# touch-24-v5.net
KiCad netlist of a schematic drawn in Altium Designer
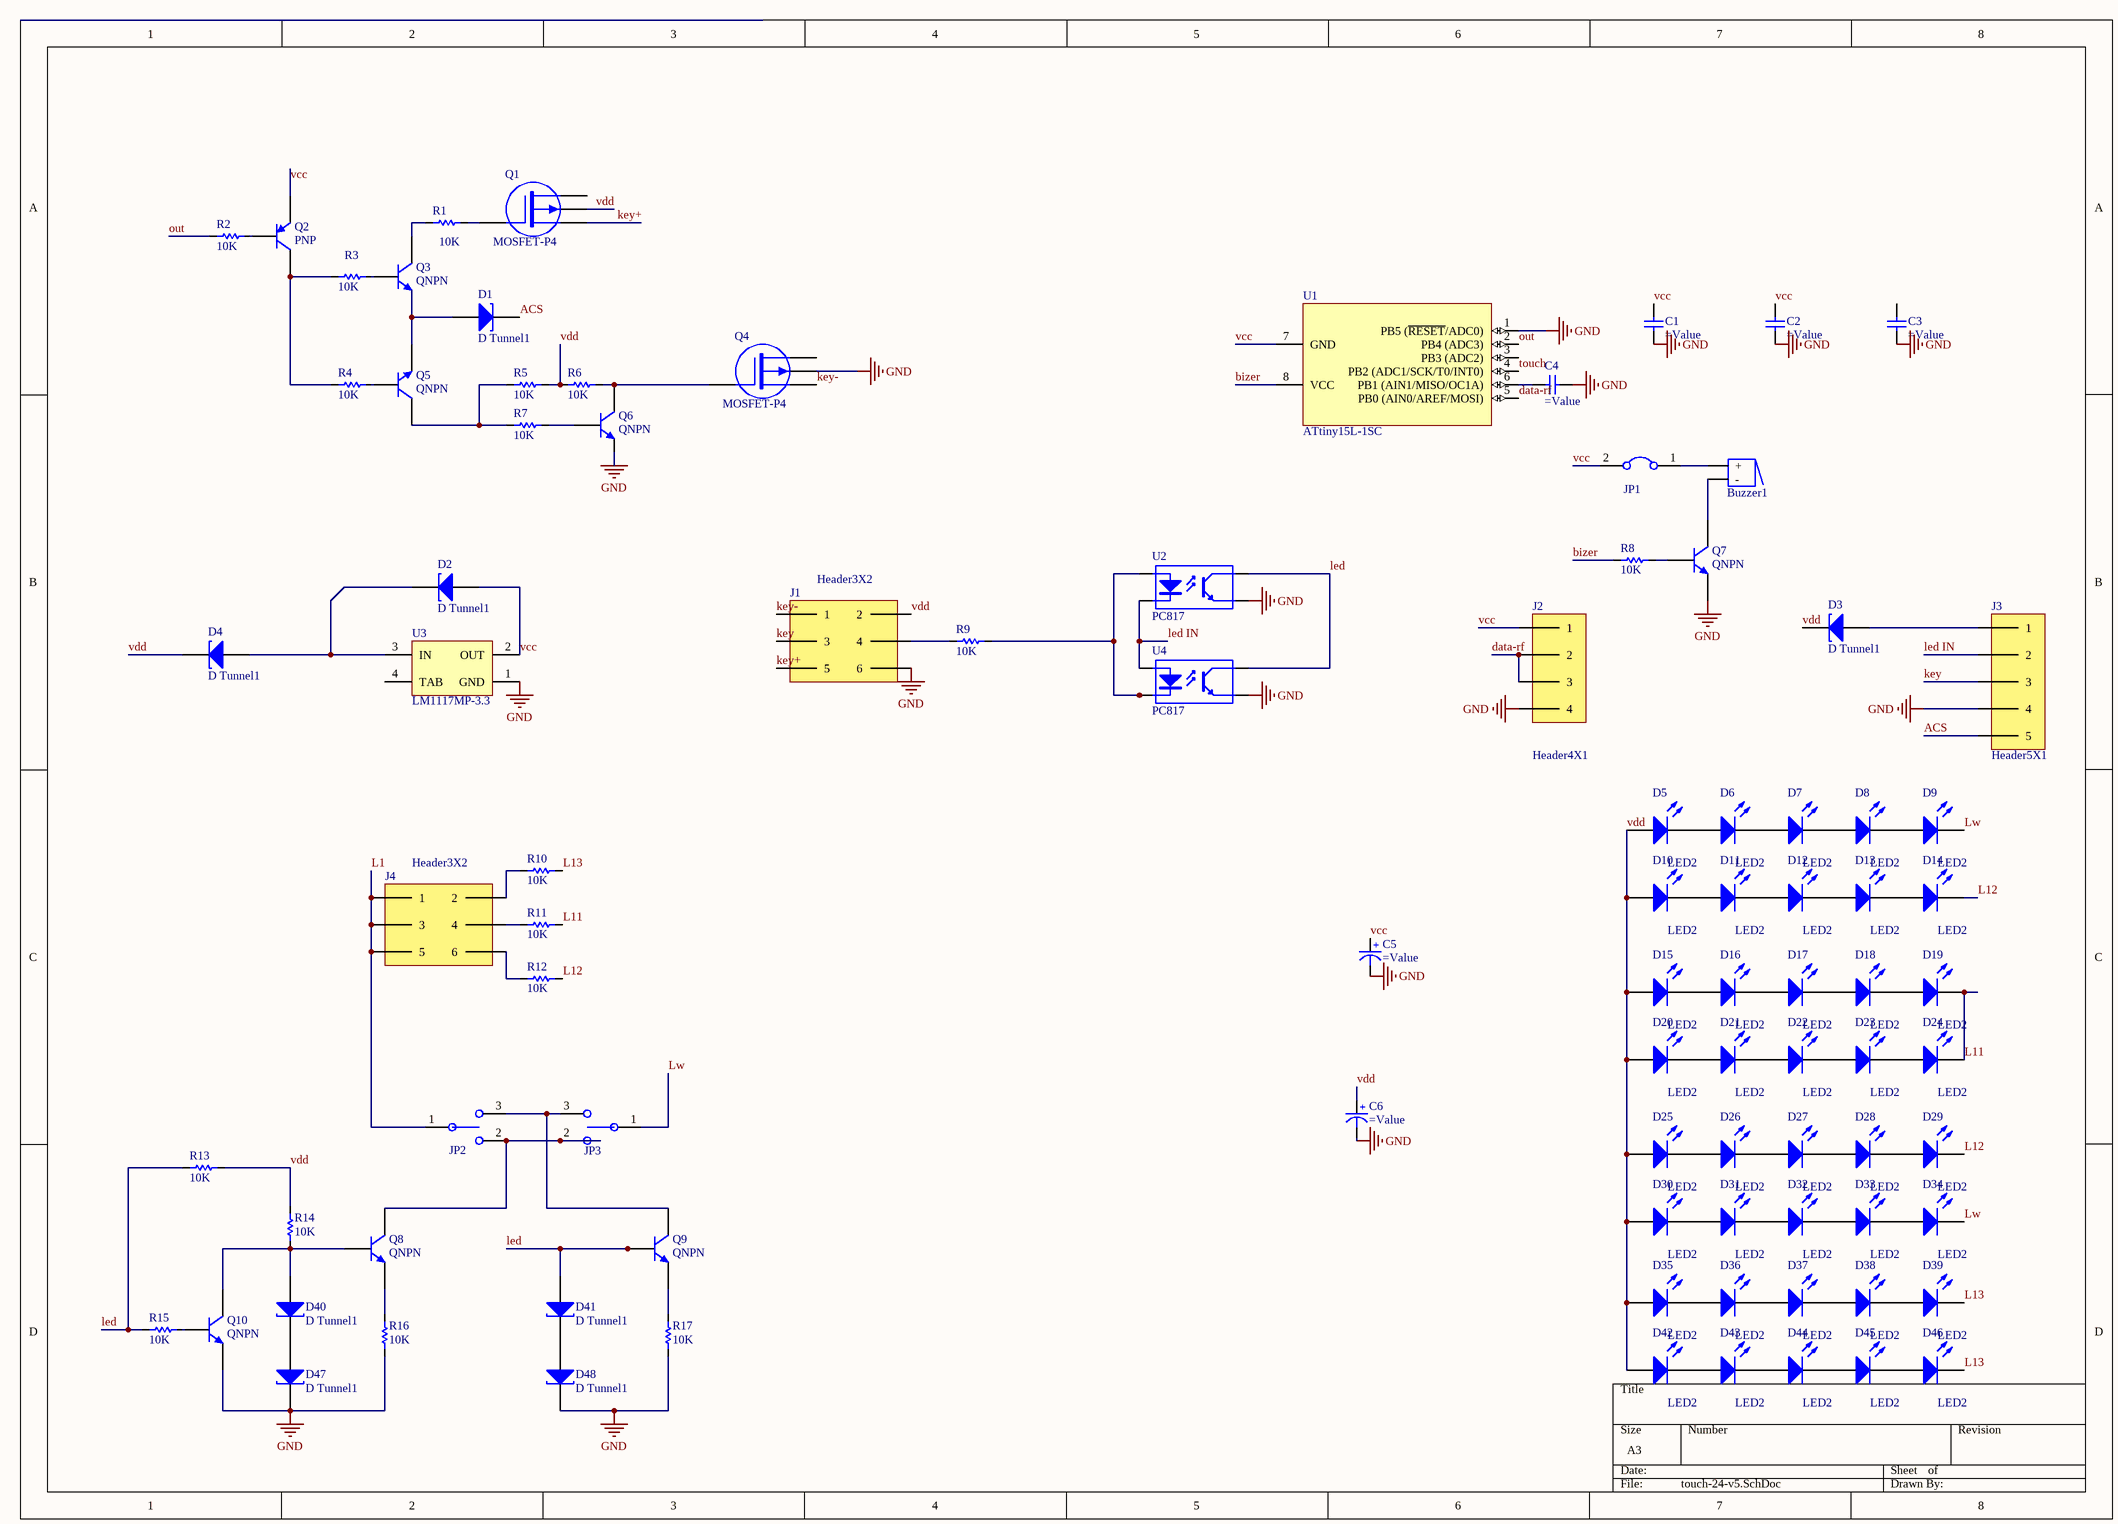
[diagram p0: touch-24-v5.SchDoc]

(export (version "E")
  (design (tool "Eeschema 10.0.6"))
  (components
    (comp (ref "Buzzer1")
      (value "Buzzer")
      (footprint "BUZZER")
      (fields (field (name "DESIGNER") "Seyed Mohsen Ghasemain"))
      (libsource (lib "PicPars.com_usefully_Library") (part "Buzzer"))
    )
    (comp (ref "C1")
      (value "~")
      (footprint "CAP 1206")
      (description "Capacitor")
      (libsource (lib "AltiumLib1") (part "Capacitor"))
    )
    (comp (ref "C2")
      (value "~")
      (footprint "CAP 1206")
      (description "Capacitor")
      (libsource (lib "AltiumLib1") (part "Capacitor"))
    )
    (comp (ref "C3")
      (value "~")
      (footprint "CAP 1206")
      (description "Capacitor")
      (libsource (lib "AltiumLib1") (part "Capacitor"))
    )
    (comp (ref "C4")
      (value "~")
      (footprint "CAP 1206")
      (description "Capacitor")
      (libsource (lib "AltiumLib1") (part "Capacitor"))
    )
    (comp (ref "C5")
      (value "~")
      (footprint "ELEC-CAP-RAD10-20")
      (description "Electrolytic Capacitor")
      (libsource (lib "AltiumLib1") (part "Capacitor Electrolytic"))
    )
    (comp (ref "C6")
      (value "~")
      (footprint "ELEC-CAP-RAD15-30")
      (description "Electrolytic Capacitor")
      (libsource (lib "AltiumLib1") (part "Capacitor Electrolytic"))
    )
    (comp (ref "D1")
      (value "D Tunnel1")
      (footprint "3.2X1.6X1.1")
      (description "Tunnel Diode - RLC Model")
      (fields (field (name "PUBLISHER") "Altium Limited"))
      (libsource (lib "Miscellaneous Devices") (part "D Tunnel1"))
    )
    (comp (ref "D2")
      (value "D Tunnel1")
      (footprint "3.2X1.6X1.1")
      (description "Tunnel Diode - RLC Model")
      (fields (field (name "PUBLISHER") "Altium Limited"))
      (libsource (lib "Miscellaneous Devices") (part "D Tunnel1"))
    )
    (comp (ref "D3")
      (value "D Tunnel1")
      (footprint "3.2X1.6X1.1")
      (description "Tunnel Diode - RLC Model")
      (fields (field (name "PUBLISHER") "Altium Limited"))
      (libsource (lib "Miscellaneous Devices") (part "D Tunnel1"))
    )
    (comp (ref "D4")
      (value "D Tunnel1")
      (footprint "3.2X1.6X1.1")
      (description "Tunnel Diode - RLC Model")
      (fields (field (name "PUBLISHER") "Altium Limited"))
      (libsource (lib "Miscellaneous Devices") (part "D Tunnel1"))
    )
    (comp (ref "D5")
      (value "LED2")
      (footprint "RES 0805 (2012X06L)")
      (description "Typical RED, GREEN, YELLOW, AMBER GaAs LED")
      (fields (field (name "PUBLISHER") "Altium Limited"))
      (libsource (lib "Miscellaneous Devices") (part "LED2"))
    )
    (comp (ref "D6")
      (value "LED2")
      (footprint "RES 0805 (2012X06L)")
      (description "Typical RED, GREEN, YELLOW, AMBER GaAs LED")
      (fields (field (name "PUBLISHER") "Altium Limited"))
      (libsource (lib "Miscellaneous Devices") (part "LED2"))
    )
    (comp (ref "D7")
      (value "LED2")
      (footprint "RES 0805 (2012X06L)")
      (description "Typical RED, GREEN, YELLOW, AMBER GaAs LED")
      (fields (field (name "PUBLISHER") "Altium Limited"))
      (libsource (lib "Miscellaneous Devices") (part "LED2"))
    )
    (comp (ref "D8")
      (value "LED2")
      (footprint "RES 0805 (2012X06L)")
      (description "Typical RED, GREEN, YELLOW, AMBER GaAs LED")
      (fields (field (name "PUBLISHER") "Altium Limited"))
      (libsource (lib "Miscellaneous Devices") (part "LED2"))
    )
    (comp (ref "D9")
      (value "LED2")
      (footprint "RES 0805 (2012X06L)")
      (description "Typical RED, GREEN, YELLOW, AMBER GaAs LED")
      (fields (field (name "PUBLISHER") "Altium Limited"))
      (libsource (lib "Miscellaneous Devices") (part "LED2"))
    )
    (comp (ref "D10")
      (value "LED2")
      (footprint "RES 0805 (2012X06L)")
      (description "Typical RED, GREEN, YELLOW, AMBER GaAs LED")
      (fields (field (name "PUBLISHER") "Altium Limited"))
      (libsource (lib "Miscellaneous Devices") (part "LED2"))
    )
    (comp (ref "D11")
      (value "LED2")
      (footprint "RES 0805 (2012X06L)")
      (description "Typical RED, GREEN, YELLOW, AMBER GaAs LED")
      (fields (field (name "PUBLISHER") "Altium Limited"))
      (libsource (lib "Miscellaneous Devices") (part "LED2"))
    )
    (comp (ref "D12")
      (value "LED2")
      (footprint "RES 0805 (2012X06L)")
      (description "Typical RED, GREEN, YELLOW, AMBER GaAs LED")
      (fields (field (name "PUBLISHER") "Altium Limited"))
      (libsource (lib "Miscellaneous Devices") (part "LED2"))
    )
    (comp (ref "D13")
      (value "LED2")
      (footprint "RES 0805 (2012X06L)")
      (description "Typical RED, GREEN, YELLOW, AMBER GaAs LED")
      (fields (field (name "PUBLISHER") "Altium Limited"))
      (libsource (lib "Miscellaneous Devices") (part "LED2"))
    )
    (comp (ref "D14")
      (value "LED2")
      (footprint "RES 0805 (2012X06L)")
      (description "Typical RED, GREEN, YELLOW, AMBER GaAs LED")
      (fields (field (name "PUBLISHER") "Altium Limited"))
      (libsource (lib "Miscellaneous Devices") (part "LED2"))
    )
    (comp (ref "D15")
      (value "LED2")
      (footprint "RES 0805 (2012X06L)")
      (description "Typical RED, GREEN, YELLOW, AMBER GaAs LED")
      (fields (field (name "PUBLISHER") "Altium Limited"))
      (libsource (lib "Miscellaneous Devices") (part "LED2"))
    )
    (comp (ref "D16")
      (value "LED2")
      (footprint "RES 0805 (2012X06L)")
      (description "Typical RED, GREEN, YELLOW, AMBER GaAs LED")
      (fields (field (name "PUBLISHER") "Altium Limited"))
      (libsource (lib "Miscellaneous Devices") (part "LED2"))
    )
    (comp (ref "D17")
      (value "LED2")
      (footprint "RES 0805 (2012X06L)")
      (description "Typical RED, GREEN, YELLOW, AMBER GaAs LED")
      (fields (field (name "PUBLISHER") "Altium Limited"))
      (libsource (lib "Miscellaneous Devices") (part "LED2"))
    )
    (comp (ref "D18")
      (value "LED2")
      (footprint "RES 0805 (2012X06L)")
      (description "Typical RED, GREEN, YELLOW, AMBER GaAs LED")
      (fields (field (name "PUBLISHER") "Altium Limited"))
      (libsource (lib "Miscellaneous Devices") (part "LED2"))
    )
    (comp (ref "D19")
      (value "LED2")
      (footprint "RES 0805 (2012X06L)")
      (description "Typical RED, GREEN, YELLOW, AMBER GaAs LED")
      (fields (field (name "PUBLISHER") "Altium Limited"))
      (libsource (lib "Miscellaneous Devices") (part "LED2"))
    )
    (comp (ref "D20")
      (value "LED2")
      (footprint "RES 0805 (2012X06L)")
      (description "Typical RED, GREEN, YELLOW, AMBER GaAs LED")
      (fields (field (name "PUBLISHER") "Altium Limited"))
      (libsource (lib "Miscellaneous Devices") (part "LED2"))
    )
    (comp (ref "D21")
      (value "LED2")
      (footprint "RES 0805 (2012X06L)")
      (description "Typical RED, GREEN, YELLOW, AMBER GaAs LED")
      (fields (field (name "PUBLISHER") "Altium Limited"))
      (libsource (lib "Miscellaneous Devices") (part "LED2"))
    )
    (comp (ref "D22")
      (value "LED2")
      (footprint "RES 0805 (2012X06L)")
      (description "Typical RED, GREEN, YELLOW, AMBER GaAs LED")
      (fields (field (name "PUBLISHER") "Altium Limited"))
      (libsource (lib "Miscellaneous Devices") (part "LED2"))
    )
    (comp (ref "D23")
      (value "LED2")
      (footprint "RES 0805 (2012X06L)")
      (description "Typical RED, GREEN, YELLOW, AMBER GaAs LED")
      (fields (field (name "PUBLISHER") "Altium Limited"))
      (libsource (lib "Miscellaneous Devices") (part "LED2"))
    )
    (comp (ref "D24")
      (value "LED2")
      (footprint "RES 0805 (2012X06L)")
      (description "Typical RED, GREEN, YELLOW, AMBER GaAs LED")
      (fields (field (name "PUBLISHER") "Altium Limited"))
      (libsource (lib "Miscellaneous Devices") (part "LED2"))
    )
    (comp (ref "D25")
      (value "LED2")
      (footprint "RES 0805 (2012X06L)")
      (description "Typical RED, GREEN, YELLOW, AMBER GaAs LED")
      (fields (field (name "PUBLISHER") "Altium Limited"))
      (libsource (lib "Miscellaneous Devices") (part "LED2"))
    )
    (comp (ref "D26")
      (value "LED2")
      (footprint "RES 0805 (2012X06L)")
      (description "Typical RED, GREEN, YELLOW, AMBER GaAs LED")
      (fields (field (name "PUBLISHER") "Altium Limited"))
      (libsource (lib "Miscellaneous Devices") (part "LED2"))
    )
    (comp (ref "D27")
      (value "LED2")
      (footprint "RES 0805 (2012X06L)")
      (description "Typical RED, GREEN, YELLOW, AMBER GaAs LED")
      (fields (field (name "PUBLISHER") "Altium Limited"))
      (libsource (lib "Miscellaneous Devices") (part "LED2"))
    )
    (comp (ref "D28")
      (value "LED2")
      (footprint "RES 0805 (2012X06L)")
      (description "Typical RED, GREEN, YELLOW, AMBER GaAs LED")
      (fields (field (name "PUBLISHER") "Altium Limited"))
      (libsource (lib "Miscellaneous Devices") (part "LED2"))
    )
    (comp (ref "D29")
      (value "LED2")
      (footprint "RES 0805 (2012X06L)")
      (description "Typical RED, GREEN, YELLOW, AMBER GaAs LED")
      (fields (field (name "PUBLISHER") "Altium Limited"))
      (libsource (lib "Miscellaneous Devices") (part "LED2"))
    )
    (comp (ref "D30")
      (value "LED2")
      (footprint "RES 0805 (2012X06L)")
      (description "Typical RED, GREEN, YELLOW, AMBER GaAs LED")
      (fields (field (name "PUBLISHER") "Altium Limited"))
      (libsource (lib "Miscellaneous Devices") (part "LED2"))
    )
    (comp (ref "D31")
      (value "LED2")
      (footprint "RES 0805 (2012X06L)")
      (description "Typical RED, GREEN, YELLOW, AMBER GaAs LED")
      (fields (field (name "PUBLISHER") "Altium Limited"))
      (libsource (lib "Miscellaneous Devices") (part "LED2"))
    )
    (comp (ref "D32")
      (value "LED2")
      (footprint "RES 0805 (2012X06L)")
      (description "Typical RED, GREEN, YELLOW, AMBER GaAs LED")
      (fields (field (name "PUBLISHER") "Altium Limited"))
      (libsource (lib "Miscellaneous Devices") (part "LED2"))
    )
    (comp (ref "D33")
      (value "LED2")
      (footprint "RES 0805 (2012X06L)")
      (description "Typical RED, GREEN, YELLOW, AMBER GaAs LED")
      (fields (field (name "PUBLISHER") "Altium Limited"))
      (libsource (lib "Miscellaneous Devices") (part "LED2"))
    )
    (comp (ref "D34")
      (value "LED2")
      (footprint "RES 0805 (2012X06L)")
      (description "Typical RED, GREEN, YELLOW, AMBER GaAs LED")
      (fields (field (name "PUBLISHER") "Altium Limited"))
      (libsource (lib "Miscellaneous Devices") (part "LED2"))
    )
    (comp (ref "D35")
      (value "LED2")
      (footprint "RES 0805 (2012X06L)")
      (description "Typical RED, GREEN, YELLOW, AMBER GaAs LED")
      (fields (field (name "PUBLISHER") "Altium Limited"))
      (libsource (lib "Miscellaneous Devices") (part "LED2"))
    )
    (comp (ref "D36")
      (value "LED2")
      (footprint "RES 0805 (2012X06L)")
      (description "Typical RED, GREEN, YELLOW, AMBER GaAs LED")
      (fields (field (name "PUBLISHER") "Altium Limited"))
      (libsource (lib "Miscellaneous Devices") (part "LED2"))
    )
    (comp (ref "D37")
      (value "LED2")
      (footprint "RES 0805 (2012X06L)")
      (description "Typical RED, GREEN, YELLOW, AMBER GaAs LED")
      (fields (field (name "PUBLISHER") "Altium Limited"))
      (libsource (lib "Miscellaneous Devices") (part "LED2"))
    )
    (comp (ref "D38")
      (value "LED2")
      (footprint "RES 0805 (2012X06L)")
      (description "Typical RED, GREEN, YELLOW, AMBER GaAs LED")
      (fields (field (name "PUBLISHER") "Altium Limited"))
      (libsource (lib "Miscellaneous Devices") (part "LED2"))
    )
    (comp (ref "D39")
      (value "LED2")
      (footprint "RES 0805 (2012X06L)")
      (description "Typical RED, GREEN, YELLOW, AMBER GaAs LED")
      (fields (field (name "PUBLISHER") "Altium Limited"))
      (libsource (lib "Miscellaneous Devices") (part "LED2"))
    )
    (comp (ref "D40")
      (value "D Tunnel1")
      (footprint "3.2X1.6X1.1")
      (description "Tunnel Diode - RLC Model")
      (fields (field (name "PUBLISHER") "Altium Limited"))
      (libsource (lib "Miscellaneous Devices") (part "D Tunnel1"))
    )
    (comp (ref "D41")
      (value "D Tunnel1")
      (footprint "3.2X1.6X1.1")
      (description "Tunnel Diode - RLC Model")
      (fields (field (name "PUBLISHER") "Altium Limited"))
      (libsource (lib "Miscellaneous Devices") (part "D Tunnel1"))
    )
    (comp (ref "D42")
      (value "LED2")
      (footprint "RES 0805 (2012X06L)")
      (description "Typical RED, GREEN, YELLOW, AMBER GaAs LED")
      (fields (field (name "PUBLISHER") "Altium Limited"))
      (libsource (lib "Miscellaneous Devices") (part "LED2"))
    )
    (comp (ref "D43")
      (value "LED2")
      (footprint "RES 0805 (2012X06L)")
      (description "Typical RED, GREEN, YELLOW, AMBER GaAs LED")
      (fields (field (name "PUBLISHER") "Altium Limited"))
      (libsource (lib "Miscellaneous Devices") (part "LED2"))
    )
    (comp (ref "D44")
      (value "LED2")
      (footprint "RES 0805 (2012X06L)")
      (description "Typical RED, GREEN, YELLOW, AMBER GaAs LED")
      (fields (field (name "PUBLISHER") "Altium Limited"))
      (libsource (lib "Miscellaneous Devices") (part "LED2"))
    )
    (comp (ref "D45")
      (value "LED2")
      (footprint "RES 0805 (2012X06L)")
      (description "Typical RED, GREEN, YELLOW, AMBER GaAs LED")
      (fields (field (name "PUBLISHER") "Altium Limited"))
      (libsource (lib "Miscellaneous Devices") (part "LED2"))
    )
    (comp (ref "D46")
      (value "LED2")
      (footprint "RES 0805 (2012X06L)")
      (description "Typical RED, GREEN, YELLOW, AMBER GaAs LED")
      (fields (field (name "PUBLISHER") "Altium Limited"))
      (libsource (lib "Miscellaneous Devices") (part "LED2"))
    )
    (comp (ref "D47")
      (value "D Tunnel1")
      (footprint "3.2X1.6X1.1")
      (description "Tunnel Diode - RLC Model")
      (fields (field (name "PUBLISHER") "Altium Limited"))
      (libsource (lib "Miscellaneous Devices") (part "D Tunnel1"))
    )
    (comp (ref "D48")
      (value "D Tunnel1")
      (footprint "3.2X1.6X1.1")
      (description "Tunnel Diode - RLC Model")
      (fields (field (name "PUBLISHER") "Altium Limited"))
      (libsource (lib "Miscellaneous Devices") (part "D Tunnel1"))
    )
    (comp (ref "J1")
      (value "Header3X2")
      (footprint "HEADER 3X2")
      (libsource (lib "AltiumLib1") (part "Header3X2"))
    )
    (comp (ref "J2")
      (value "Header4X1")
      (footprint "HEADER 4X1")
      (libsource (lib "AltiumLib1") (part "Header4X1"))
    )
    (comp (ref "J3")
      (value "Header5X1")
      (footprint "HEADER 5X1")
      (libsource (lib "AltiumLib1") (part "Header5X1"))
    )
    (comp (ref "J4")
      (value "Header3X2")
      (footprint "HEADER 3X2")
      (libsource (lib "AltiumLib1") (part "Header3X2"))
    )
    (comp (ref "JP1")
      (value "Jumper")
      (footprint "Header 2X1")
      (libsource (lib "AltiumLib1") (part "Jumper"))
    )
    (comp (ref "JP2")
      (value "Jumper Selector")
      (footprint "Jumper Selector")
      (libsource (lib "") (part "Jumper Selector_1"))
    )
    (comp (ref "JP3")
      (value "Jumper Selector")
      (footprint "Jumper Selector")
      (libsource (lib "AltiumLib1") (part "Jumper Selector"))
    )
    (comp (ref "Q1")
      (value "MOSFET-P4")
      (footprint "SOT223_N")
      (description "P-Channel MOSFET, Externally Terminated Substrate")
      (fields (field (name "PUBLISHER") "Altium Limited"))
      (libsource (lib "Miscellaneous Devices") (part "MOSFET-P4"))
    )
    (comp (ref "Q2")
      (value "PNP")
      (footprint "SOT-23B_N")
      (description "PNP Bipolar Transistor")
      (fields (field (name "PUBLISHER") "Altium Limited"))
      (libsource (lib "Miscellaneous Devices") (part "PNP"))
    )
    (comp (ref "Q3")
      (value "QNPN")
      (footprint "SOT-23B_L")
      (description "NPN Bipolar Transistor")
      (fields (field (name "PUBLISHER") "Altium Limited"))
      (libsource (lib "Miscellaneous Devices") (part "QNPN"))
    )
    (comp (ref "Q4")
      (value "MOSFET-P4")
      (footprint "SOT223_N")
      (description "P-Channel MOSFET, Externally Terminated Substrate")
      (fields (field (name "PUBLISHER") "Altium Limited"))
      (libsource (lib "Miscellaneous Devices") (part "MOSFET-P4"))
    )
    (comp (ref "Q5")
      (value "QNPN")
      (footprint "SOT-23B_L")
      (description "NPN Bipolar Transistor")
      (fields (field (name "PUBLISHER") "Altium Limited"))
      (libsource (lib "Miscellaneous Devices") (part "QNPN"))
    )
    (comp (ref "Q6")
      (value "QNPN")
      (footprint "SOT-23B_L")
      (description "NPN Bipolar Transistor")
      (fields (field (name "PUBLISHER") "Altium Limited"))
      (libsource (lib "Miscellaneous Devices") (part "QNPN"))
    )
    (comp (ref "Q7")
      (value "QNPN")
      (footprint "SOT-23B_L")
      (description "NPN Bipolar Transistor")
      (fields (field (name "PUBLISHER") "Altium Limited"))
      (libsource (lib "Miscellaneous Devices") (part "QNPN"))
    )
    (comp (ref "Q8")
      (value "QNPN")
      (footprint "SOT-23B_L")
      (description "NPN Bipolar Transistor")
      (fields (field (name "PUBLISHER") "Altium Limited"))
      (libsource (lib "Miscellaneous Devices") (part "QNPN"))
    )
    (comp (ref "Q9")
      (value "QNPN")
      (footprint "SOT-23B_L")
      (description "NPN Bipolar Transistor")
      (fields (field (name "PUBLISHER") "Altium Limited"))
      (libsource (lib "Miscellaneous Devices") (part "QNPN"))
    )
    (comp (ref "Q10")
      (value "QNPN")
      (footprint "SOT-23B_L")
      (description "NPN Bipolar Transistor")
      (fields (field (name "PUBLISHER") "Altium Limited"))
      (libsource (lib "Miscellaneous Devices") (part "QNPN"))
    )
    (comp (ref "R1")
      (value "10K")
      (footprint "RES 1206 (3216X08L)")
      (description "Resistor")
      (fields (field (name "TOLERANCE") "5%") (field (name "POWER") "1/4 W"))
      (libsource (lib "AltiumLib1") (part "Resistor"))
    )
    (comp (ref "R2")
      (value "10K")
      (footprint "RES 1206 (3216X08L)")
      (description "Resistor")
      (fields (field (name "TOLERANCE") "5%") (field (name "POWER") "1/4 W"))
      (libsource (lib "AltiumLib1") (part "Resistor"))
    )
    (comp (ref "R3")
      (value "10K")
      (footprint "RES 1206 (3216X08L)")
      (description "Resistor")
      (fields (field (name "TOLERANCE") "5%") (field (name "POWER") "1/4 W"))
      (libsource (lib "AltiumLib1") (part "Resistor"))
    )
    (comp (ref "R4")
      (value "10K")
      (footprint "RES 1206 (3216X08L)")
      (description "Resistor")
      (fields (field (name "TOLERANCE") "5%") (field (name "POWER") "1/4 W"))
      (libsource (lib "AltiumLib1") (part "Resistor"))
    )
    (comp (ref "R5")
      (value "10K")
      (footprint "RES 1206 (3216X08L)")
      (description "Resistor")
      (fields (field (name "TOLERANCE") "5%") (field (name "POWER") "1/4 W"))
      (libsource (lib "AltiumLib1") (part "Resistor"))
    )
    (comp (ref "R6")
      (value "10K")
      (footprint "RES 1206 (3216X08L)")
      (description "Resistor")
      (fields (field (name "TOLERANCE") "5%") (field (name "POWER") "1/4 W"))
      (libsource (lib "AltiumLib1") (part "Resistor"))
    )
    (comp (ref "R7")
      (value "10K")
      (footprint "RES 1206 (3216X08L)")
      (description "Resistor")
      (fields (field (name "TOLERANCE") "5%") (field (name "POWER") "1/4 W"))
      (libsource (lib "AltiumLib1") (part "Resistor"))
    )
    (comp (ref "R8")
      (value "10K")
      (footprint "RES 1206 (3216X08L)")
      (description "Resistor")
      (fields (field (name "TOLERANCE") "5%") (field (name "POWER") "1/4 W"))
      (libsource (lib "AltiumLib1") (part "Resistor"))
    )
    (comp (ref "R9")
      (value "10K")
      (footprint "RES 1206 (3216X08L)")
      (description "Resistor")
      (fields (field (name "TOLERANCE") "5%") (field (name "POWER") "1/4 W"))
      (libsource (lib "AltiumLib1") (part "Resistor"))
    )
    (comp (ref "R10")
      (value "10K")
      (footprint "RES 1206 (3216X08L)")
      (description "Resistor")
      (fields (field (name "TOLERANCE") "5%") (field (name "POWER") "1/4 W"))
      (libsource (lib "AltiumLib1") (part "Resistor"))
    )
    (comp (ref "R11")
      (value "10K")
      (footprint "RES 1206 (3216X08L)")
      (description "Resistor")
      (fields (field (name "TOLERANCE") "5%") (field (name "POWER") "1/4 W"))
      (libsource (lib "AltiumLib1") (part "Resistor"))
    )
    (comp (ref "R12")
      (value "10K")
      (footprint "RES 1206 (3216X08L)")
      (description "Resistor")
      (fields (field (name "TOLERANCE") "5%") (field (name "POWER") "1/4 W"))
      (libsource (lib "AltiumLib1") (part "Resistor"))
    )
    (comp (ref "R13")
      (value "10K")
      (footprint "RES 1206 (3216X08L)")
      (description "Resistor")
      (fields (field (name "TOLERANCE") "5%") (field (name "POWER") "1/4 W"))
      (libsource (lib "AltiumLib1") (part "Resistor"))
    )
    (comp (ref "R14")
      (value "10K")
      (footprint "RES 1206 (3216X08L)")
      (description "Resistor")
      (fields (field (name "TOLERANCE") "5%") (field (name "POWER") "1/4 W"))
      (libsource (lib "AltiumLib1") (part "Resistor"))
    )
    (comp (ref "R15")
      (value "10K")
      (footprint "RES 1206 (3216X08L)")
      (description "Resistor")
      (fields (field (name "TOLERANCE") "5%") (field (name "POWER") "1/4 W"))
      (libsource (lib "AltiumLib1") (part "Resistor"))
    )
    (comp (ref "R16")
      (value "10K")
      (footprint "RES 1206 (3216X08L)")
      (description "Resistor")
      (fields (field (name "TOLERANCE") "5%") (field (name "POWER") "1/4 W"))
      (libsource (lib "AltiumLib1") (part "Resistor"))
    )
    (comp (ref "R17")
      (value "10K")
      (footprint "RES 1206 (3216X08L)")
      (description "Resistor")
      (fields (field (name "TOLERANCE") "5%") (field (name "POWER") "1/4 W"))
      (libsource (lib "AltiumLib1") (part "Resistor"))
    )
    (comp (ref "U1")
      (value "ATtiny15L-1SC")
      (footprint "8S2_N")
      (description "8-Bit AVR Microcontroller with 1K Byte of Flash Memory")
      (fields (field (name "PUBLISHER") "Altium Limited"))
      (libsource (lib "Atmel Microcontroller 8-Bit AVR") (part "ATtiny15L-1SC"))
    )
    (comp (ref "U2")
      (value "PC817")
      (footprint "DIP4")
      (description "4-Pin Phototransistor Optocoupler")
      (libsource (lib "AltiumLib1") (part "OPTCOUPLER_01"))
    )
    (comp (ref "U3")
      (value "LM1117MP-3.3")
      (footprint "Miscellaneous Devices:SOT89L")
      (description "800mA Low-Dropout Linear Regulator")
      (fields
        (field (name "MANUFACTURER") "National Semiconductor")
        (field (name "DIGIKEYPARTNUMBER") "LM1117MP-3.3CT-ND")
        (field (name "PUBLISHER") "Altium Limited")
      )
      (libsource (lib "NSC LDO") (part "LM1117MP-3.3"))
    )
    (comp (ref "U4")
      (value "PC817")
      (footprint "DIP4")
      (description "4-Pin Phototransistor Optocoupler")
      (libsource (lib "AltiumLib1") (part "OPTCOUPLER_01"))
    )
  )
  (nets
    (net (code "1") (name "/ACS") (class "Default")
      (node (ref "D1") (pin "2") (pinfunction "K_2") (pintype "passive"))
      (node (ref "J3") (pin "5") (pinfunction "5_5") (pintype "passive"))
    )
    (net (code "2") (name "/L1") (class "Default")
      (node (ref "J4") (pin "1") (pinfunction "1_1") (pintype "passive"))
      (node (ref "J4") (pin "3") (pinfunction "3_3") (pintype "passive"))
      (node (ref "J4") (pin "5") (pinfunction "5_5") (pintype "passive"))
      (node (ref "JP2") (pin "1") (pinfunction "1_1") (pintype "passive"))
    )
    (net (code "3") (name "/L11") (class "Default")
      (node (ref "D19") (pin "2") (pinfunction "K_2") (pintype "passive"))
      (node (ref "D24") (pin "2") (pinfunction "K_2") (pintype "passive"))
      (node (ref "R11") (pin "2") (pinfunction "2_2") (pintype "passive"))
    )
    (net (code "4") (name "/L12") (class "Default")
      (node (ref "D14") (pin "2") (pinfunction "K_2") (pintype "passive"))
      (node (ref "D29") (pin "2") (pinfunction "K_2") (pintype "passive"))
      (node (ref "R12") (pin "2") (pinfunction "2_2") (pintype "passive"))
    )
    (net (code "5") (name "/L13") (class "Default")
      (node (ref "D39") (pin "2") (pinfunction "K_2") (pintype "passive"))
      (node (ref "D46") (pin "2") (pinfunction "K_2") (pintype "passive"))
      (node (ref "R10") (pin "2") (pinfunction "2_2") (pintype "passive"))
    )
    (net (code "6") (name "/Lw") (class "Default")
      (node (ref "D34") (pin "2") (pinfunction "K_2") (pintype "passive"))
      (node (ref "D9") (pin "2") (pinfunction "K_2") (pintype "passive"))
      (node (ref "JP3") (pin "1") (pinfunction "1_1") (pintype "passive"))
    )
    (net (code "7") (name "/bizer") (class "Default")
      (node (ref "R8") (pin "1") (pinfunction "1_1") (pintype "passive"))
      (node (ref "U1") (pin "8") (pinfunction "VCC_8") (pintype "power_in"))
    )
    (net (code "8") (name "/data-rf") (class "Default")
      (node (ref "J2") (pin "2") (pinfunction "2_2") (pintype "passive"))
      (node (ref "J2") (pin "3") (pinfunction "3_3") (pintype "passive"))
      (node (ref "U1") (pin "5") (pinfunction "PB0_(AIN0/AREF/MOSI)_5") (pintype "bidirectional"))
    )
    (net (code "9") (name "/key") (class "Default")
      (node (ref "J1") (pin "3") (pinfunction "3_3") (pintype "passive"))
      (node (ref "J3") (pin "3") (pinfunction "3_3") (pintype "passive"))
    )
    (net (code "10") (name "/key+") (class "Default")
      (node (ref "J1") (pin "5") (pinfunction "5_5") (pintype "passive"))
      (node (ref "Q1") (pin "4") (pinfunction "S_4") (pintype "passive"))
    )
    (net (code "11") (name "/key-") (class "Default")
      (node (ref "J1") (pin "1") (pinfunction "1_1") (pintype "passive"))
      (node (ref "Q4") (pin "4") (pinfunction "S_4") (pintype "passive"))
    )
    (net (code "12") (name "/led") (class "Default")
      (node (ref "D41") (pin "1") (pinfunction "A_1") (pintype "passive"))
      (node (ref "Q9") (pin "2") (pinfunction "B_2") (pintype "passive"))
      (node (ref "R13") (pin "1") (pinfunction "1_1") (pintype "passive"))
      (node (ref "R15") (pin "1") (pinfunction "1_1") (pintype "passive"))
      (node (ref "U2") (pin "4") (pinfunction "C_4") (pintype "passive"))
      (node (ref "U4") (pin "4") (pinfunction "C_4") (pintype "passive"))
    )
    (net (code "13") (name "/led IN") (class "Default")
      (node (ref "J3") (pin "2") (pinfunction "2_2") (pintype "passive"))
      (node (ref "U2") (pin "2") (pinfunction "K_2") (pintype "passive"))
      (node (ref "U4") (pin "1") (pinfunction "A_1") (pintype "passive"))
    )
    (net (code "14") (name "/out") (class "Default")
      (node (ref "R2") (pin "1") (pinfunction "1_1") (pintype "passive"))
      (node (ref "U1") (pin "2") (pinfunction "PB4_(ADC3)_2") (pintype "bidirectional"))
    )
    (net (code "15") (name "/touch") (class "Default")
      (node (ref "U1") (pin "4") (pinfunction "PB2_(ADC1/SCK/T0/INT0)_4") (pintype "bidirectional"))
    )
    (net (code "16") (name "/vcc") (class "Default")
      (node (ref "C1") (pin "2") (pinfunction "-_2") (pintype "passive"))
      (node (ref "C2") (pin "2") (pinfunction "-_2") (pintype "passive"))
      (node (ref "C5") (pin "2") (pinfunction "+_2") (pintype "passive"))
      (node (ref "D2") (pin "1") (pinfunction "A_1") (pintype "passive"))
      (node (ref "J2") (pin "1") (pinfunction "1_1") (pintype "passive"))
      (node (ref "JP1") (pin "2") (pinfunction "2_2") (pintype "passive"))
      (node (ref "Q2") (pin "3") (pinfunction "E_3") (pintype "passive"))
      (node (ref "U1") (pin "7") (pinfunction "GND_7") (pintype "power_in"))
      (node (ref "U3") (pin "2") (pinfunction "OUT_2") (pintype "power_in"))
    )
    (net (code "17") (name "/vdd") (class "Default")
      (node (ref "C6") (pin "2") (pinfunction "+_2") (pintype "passive"))
      (node (ref "D10") (pin "1") (pinfunction "A_1") (pintype "passive"))
      (node (ref "D15") (pin "1") (pinfunction "A_1") (pintype "passive"))
      (node (ref "D20") (pin "1") (pinfunction "A_1") (pintype "passive"))
      (node (ref "D25") (pin "1") (pinfunction "A_1") (pintype "passive"))
      (node (ref "D3") (pin "2") (pinfunction "K_2") (pintype "passive"))
      (node (ref "D30") (pin "1") (pinfunction "A_1") (pintype "passive"))
      (node (ref "D35") (pin "1") (pinfunction "A_1") (pintype "passive"))
      (node (ref "D4") (pin "2") (pinfunction "K_2") (pintype "passive"))
      (node (ref "D42") (pin "1") (pinfunction "A_1") (pintype "passive"))
      (node (ref "D5") (pin "1") (pinfunction "A_1") (pintype "passive"))
      (node (ref "J1") (pin "2") (pinfunction "2_2") (pintype "passive"))
      (node (ref "Q1") (pin "3") (pinfunction "U_3") (pintype "passive"))
      (node (ref "R13") (pin "2") (pinfunction "2_2") (pintype "passive"))
      (node (ref "R14") (pin "2") (pinfunction "2_2") (pintype "passive"))
      (node (ref "R5") (pin "2") (pinfunction "2_2") (pintype "passive"))
      (node (ref "R6") (pin "1") (pinfunction "1_1") (pintype "passive"))
    )
    (net (code "18") (name "GND") (class "Default")
      (node (ref "C1") (pin "1") (pinfunction "+_1") (pintype "passive"))
      (node (ref "C2") (pin "1") (pinfunction "+_1") (pintype "passive"))
      (node (ref "C3") (pin "1") (pinfunction "+_1") (pintype "passive"))
      (node (ref "C4") (pin "1") (pinfunction "+_1") (pintype "passive"))
      (node (ref "C5") (pin "1") (pinfunction "-_1") (pintype "passive"))
      (node (ref "C6") (pin "1") (pinfunction "-_1") (pintype "passive"))
      (node (ref "D47") (pin "2") (pinfunction "K_2") (pintype "passive"))
      (node (ref "D48") (pin "2") (pinfunction "K_2") (pintype "passive"))
      (node (ref "J1") (pin "6") (pinfunction "6_6") (pintype "passive"))
      (node (ref "J2") (pin "4") (pinfunction "4_4") (pintype "passive"))
      (node (ref "J3") (pin "4") (pinfunction "4_4") (pintype "passive"))
      (node (ref "Q10") (pin "3") (pinfunction "E_3") (pintype "passive"))
      (node (ref "Q4") (pin "3") (pinfunction "U_3") (pintype "passive"))
      (node (ref "Q6") (pin "3") (pinfunction "E_3") (pintype "passive"))
      (node (ref "Q7") (pin "3") (pinfunction "E_3") (pintype "passive"))
      (node (ref "R16") (pin "1") (pinfunction "1_1") (pintype "passive"))
      (node (ref "R17") (pin "1") (pinfunction "1_1") (pintype "passive"))
      (node (ref "U1") (pin "1") (pinfunction "PB5_(~{RESET}/ADC0)_1") (pintype "bidirectional"))
      (node (ref "U2") (pin "3") (pinfunction "E_3") (pintype "passive"))
      (node (ref "U3") (pin "1") (pinfunction "GND_1") (pintype "power_in"))
      (node (ref "U4") (pin "3") (pinfunction "E_3") (pintype "passive"))
    )
    (net (code "19") (name "Net-(Buzzer1-+)") (class "Default")
      (node (ref "Buzzer1") (pin "1") (pinfunction "+_1") (pintype "passive"))
      (node (ref "JP1") (pin "1") (pinfunction "1_1") (pintype "passive"))
    )
    (net (code "20") (name "Net-(Buzzer1--)") (class "Default")
      (node (ref "Buzzer1") (pin "2") (pinfunction "-_2") (pintype "passive"))
      (node (ref "Q7") (pin "1") (pinfunction "C_1") (pintype "passive"))
    )
    (net (code "21") (name "Net-(C4--)") (class "Default")
      (node (ref "C4") (pin "2") (pinfunction "-_2") (pintype "passive"))
      (node (ref "U1") (pin "6") (pinfunction "PB1_(AIN1/MISO/OC1A)_6") (pintype "bidirectional"))
    )
    (net (code "22") (name "Net-(D1-A)") (class "Default")
      (node (ref "D1") (pin "1") (pinfunction "A_1") (pintype "passive"))
      (node (ref "Q3") (pin "3") (pinfunction "E_3") (pintype "passive"))
      (node (ref "Q5") (pin "3") (pinfunction "E_3") (pintype "passive"))
    )
    (net (code "23") (name "Net-(D2-K)") (class "Default")
      (node (ref "D2") (pin "2") (pinfunction "K_2") (pintype "passive"))
      (node (ref "D4") (pin "1") (pinfunction "A_1") (pintype "passive"))
      (node (ref "U3") (pin "3") (pinfunction "IN_3") (pintype "power_in"))
    )
    (net (code "24") (name "Net-(D3-A)") (class "Default")
      (node (ref "D3") (pin "1") (pinfunction "A_1") (pintype "passive"))
      (node (ref "J3") (pin "1") (pinfunction "1_1") (pintype "passive"))
    )
    (net (code "25") (name "Net-(D5-K)") (class "Default")
      (node (ref "D5") (pin "2") (pinfunction "K_2") (pintype "passive"))
      (node (ref "D6") (pin "1") (pinfunction "A_1") (pintype "passive"))
    )
    (net (code "26") (name "Net-(D6-K)") (class "Default")
      (node (ref "D6") (pin "2") (pinfunction "K_2") (pintype "passive"))
      (node (ref "D7") (pin "1") (pinfunction "A_1") (pintype "passive"))
    )
    (net (code "27") (name "Net-(D7-K)") (class "Default")
      (node (ref "D7") (pin "2") (pinfunction "K_2") (pintype "passive"))
      (node (ref "D8") (pin "1") (pinfunction "A_1") (pintype "passive"))
    )
    (net (code "28") (name "Net-(D8-K)") (class "Default")
      (node (ref "D8") (pin "2") (pinfunction "K_2") (pintype "passive"))
      (node (ref "D9") (pin "1") (pinfunction "A_1") (pintype "passive"))
    )
    (net (code "29") (name "Net-(D10-K)") (class "Default")
      (node (ref "D10") (pin "2") (pinfunction "K_2") (pintype "passive"))
      (node (ref "D11") (pin "1") (pinfunction "A_1") (pintype "passive"))
    )
    (net (code "30") (name "Net-(D11-K)") (class "Default")
      (node (ref "D11") (pin "2") (pinfunction "K_2") (pintype "passive"))
      (node (ref "D12") (pin "1") (pinfunction "A_1") (pintype "passive"))
    )
    (net (code "31") (name "Net-(D12-K)") (class "Default")
      (node (ref "D12") (pin "2") (pinfunction "K_2") (pintype "passive"))
      (node (ref "D13") (pin "1") (pinfunction "A_1") (pintype "passive"))
    )
    (net (code "32") (name "Net-(D13-K)") (class "Default")
      (node (ref "D13") (pin "2") (pinfunction "K_2") (pintype "passive"))
      (node (ref "D14") (pin "1") (pinfunction "A_1") (pintype "passive"))
    )
    (net (code "33") (name "Net-(D15-K)") (class "Default")
      (node (ref "D15") (pin "2") (pinfunction "K_2") (pintype "passive"))
      (node (ref "D16") (pin "1") (pinfunction "A_1") (pintype "passive"))
    )
    (net (code "34") (name "Net-(D16-K)") (class "Default")
      (node (ref "D16") (pin "2") (pinfunction "K_2") (pintype "passive"))
      (node (ref "D17") (pin "1") (pinfunction "A_1") (pintype "passive"))
    )
    (net (code "35") (name "Net-(D17-K)") (class "Default")
      (node (ref "D17") (pin "2") (pinfunction "K_2") (pintype "passive"))
      (node (ref "D18") (pin "1") (pinfunction "A_1") (pintype "passive"))
    )
    (net (code "36") (name "Net-(D18-K)") (class "Default")
      (node (ref "D18") (pin "2") (pinfunction "K_2") (pintype "passive"))
      (node (ref "D19") (pin "1") (pinfunction "A_1") (pintype "passive"))
    )
    (net (code "37") (name "Net-(D20-K)") (class "Default")
      (node (ref "D20") (pin "2") (pinfunction "K_2") (pintype "passive"))
      (node (ref "D21") (pin "1") (pinfunction "A_1") (pintype "passive"))
    )
    (net (code "38") (name "Net-(D21-K)") (class "Default")
      (node (ref "D21") (pin "2") (pinfunction "K_2") (pintype "passive"))
      (node (ref "D22") (pin "1") (pinfunction "A_1") (pintype "passive"))
    )
    (net (code "39") (name "Net-(D22-K)") (class "Default")
      (node (ref "D22") (pin "2") (pinfunction "K_2") (pintype "passive"))
      (node (ref "D23") (pin "1") (pinfunction "A_1") (pintype "passive"))
    )
    (net (code "40") (name "Net-(D23-K)") (class "Default")
      (node (ref "D23") (pin "2") (pinfunction "K_2") (pintype "passive"))
      (node (ref "D24") (pin "1") (pinfunction "A_1") (pintype "passive"))
    )
    (net (code "41") (name "Net-(D25-K)") (class "Default")
      (node (ref "D25") (pin "2") (pinfunction "K_2") (pintype "passive"))
      (node (ref "D26") (pin "1") (pinfunction "A_1") (pintype "passive"))
    )
    (net (code "42") (name "Net-(D26-K)") (class "Default")
      (node (ref "D26") (pin "2") (pinfunction "K_2") (pintype "passive"))
      (node (ref "D27") (pin "1") (pinfunction "A_1") (pintype "passive"))
    )
    (net (code "43") (name "Net-(D27-K)") (class "Default")
      (node (ref "D27") (pin "2") (pinfunction "K_2") (pintype "passive"))
      (node (ref "D28") (pin "1") (pinfunction "A_1") (pintype "passive"))
    )
    (net (code "44") (name "Net-(D28-K)") (class "Default")
      (node (ref "D28") (pin "2") (pinfunction "K_2") (pintype "passive"))
      (node (ref "D29") (pin "1") (pinfunction "A_1") (pintype "passive"))
    )
    (net (code "45") (name "Net-(D30-K)") (class "Default")
      (node (ref "D30") (pin "2") (pinfunction "K_2") (pintype "passive"))
      (node (ref "D31") (pin "1") (pinfunction "A_1") (pintype "passive"))
    )
    (net (code "46") (name "Net-(D31-K)") (class "Default")
      (node (ref "D31") (pin "2") (pinfunction "K_2") (pintype "passive"))
      (node (ref "D32") (pin "1") (pinfunction "A_1") (pintype "passive"))
    )
    (net (code "47") (name "Net-(D32-K)") (class "Default")
      (node (ref "D32") (pin "2") (pinfunction "K_2") (pintype "passive"))
      (node (ref "D33") (pin "1") (pinfunction "A_1") (pintype "passive"))
    )
    (net (code "48") (name "Net-(D33-K)") (class "Default")
      (node (ref "D33") (pin "2") (pinfunction "K_2") (pintype "passive"))
      (node (ref "D34") (pin "1") (pinfunction "A_1") (pintype "passive"))
    )
    (net (code "49") (name "Net-(D35-K)") (class "Default")
      (node (ref "D35") (pin "2") (pinfunction "K_2") (pintype "passive"))
      (node (ref "D36") (pin "1") (pinfunction "A_1") (pintype "passive"))
    )
    (net (code "50") (name "Net-(D36-K)") (class "Default")
      (node (ref "D36") (pin "2") (pinfunction "K_2") (pintype "passive"))
      (node (ref "D37") (pin "1") (pinfunction "A_1") (pintype "passive"))
    )
    (net (code "51") (name "Net-(D37-K)") (class "Default")
      (node (ref "D37") (pin "2") (pinfunction "K_2") (pintype "passive"))
      (node (ref "D38") (pin "1") (pinfunction "A_1") (pintype "passive"))
    )
    (net (code "52") (name "Net-(D38-K)") (class "Default")
      (node (ref "D38") (pin "2") (pinfunction "K_2") (pintype "passive"))
      (node (ref "D39") (pin "1") (pinfunction "A_1") (pintype "passive"))
    )
    (net (code "53") (name "Net-(D40-A)") (class "Default")
      (node (ref "D40") (pin "1") (pinfunction "A_1") (pintype "passive"))
      (node (ref "Q10") (pin "1") (pinfunction "C_1") (pintype "passive"))
      (node (ref "Q8") (pin "2") (pinfunction "B_2") (pintype "passive"))
      (node (ref "R14") (pin "1") (pinfunction "1_1") (pintype "passive"))
    )
    (net (code "54") (name "Net-(D40-K)") (class "Default")
      (node (ref "D40") (pin "2") (pinfunction "K_2") (pintype "passive"))
      (node (ref "D47") (pin "1") (pinfunction "A_1") (pintype "passive"))
    )
    (net (code "55") (name "Net-(D41-K)") (class "Default")
      (node (ref "D41") (pin "2") (pinfunction "K_2") (pintype "passive"))
      (node (ref "D48") (pin "1") (pinfunction "A_1") (pintype "passive"))
    )
    (net (code "56") (name "Net-(D42-K)") (class "Default")
      (node (ref "D42") (pin "2") (pinfunction "K_2") (pintype "passive"))
      (node (ref "D43") (pin "1") (pinfunction "A_1") (pintype "passive"))
    )
    (net (code "57") (name "Net-(D43-K)") (class "Default")
      (node (ref "D43") (pin "2") (pinfunction "K_2") (pintype "passive"))
      (node (ref "D44") (pin "1") (pinfunction "A_1") (pintype "passive"))
    )
    (net (code "58") (name "Net-(D44-K)") (class "Default")
      (node (ref "D44") (pin "2") (pinfunction "K_2") (pintype "passive"))
      (node (ref "D45") (pin "1") (pinfunction "A_1") (pintype "passive"))
    )
    (net (code "59") (name "Net-(D45-K)") (class "Default")
      (node (ref "D45") (pin "2") (pinfunction "K_2") (pintype "passive"))
      (node (ref "D46") (pin "1") (pinfunction "A_1") (pintype "passive"))
    )
    (net (code "60") (name "Net-(J1-Pad4)") (class "Default")
      (node (ref "J1") (pin "4") (pinfunction "4_4") (pintype "passive"))
      (node (ref "R9") (pin "1") (pinfunction "1_1") (pintype "passive"))
    )
    (net (code "61") (name "Net-(J4-Pad2)") (class "Default")
      (node (ref "J4") (pin "2") (pinfunction "2_2") (pintype "passive"))
      (node (ref "R10") (pin "1") (pinfunction "1_1") (pintype "passive"))
    )
    (net (code "62") (name "Net-(J4-Pad4)") (class "Default")
      (node (ref "J4") (pin "4") (pinfunction "4_4") (pintype "passive"))
      (node (ref "R11") (pin "1") (pinfunction "1_1") (pintype "passive"))
    )
    (net (code "63") (name "Net-(J4-Pad6)") (class "Default")
      (node (ref "J4") (pin "6") (pinfunction "6_6") (pintype "passive"))
      (node (ref "R12") (pin "1") (pinfunction "1_1") (pintype "passive"))
    )
    (net (code "64") (name "Net-(Q1-G)") (class "Default")
      (node (ref "Q1") (pin "1") (pinfunction "G_1") (pintype "passive"))
      (node (ref "R1") (pin "2") (pinfunction "2_2") (pintype "passive"))
    )
    (net (code "65") (name "Net-(Q2-B)") (class "Default")
      (node (ref "Q2") (pin "2") (pinfunction "B_2") (pintype "passive"))
      (node (ref "R2") (pin "2") (pinfunction "2_2") (pintype "passive"))
    )
    (net (code "66") (name "Net-(Q2-C)") (class "Default")
      (node (ref "Q2") (pin "1") (pinfunction "C_1") (pintype "passive"))
      (node (ref "R3") (pin "1") (pinfunction "1_1") (pintype "passive"))
      (node (ref "R4") (pin "1") (pinfunction "1_1") (pintype "passive"))
    )
    (net (code "67") (name "Net-(Q3-B)") (class "Default")
      (node (ref "Q3") (pin "2") (pinfunction "B_2") (pintype "passive"))
      (node (ref "R3") (pin "2") (pinfunction "2_2") (pintype "passive"))
    )
    (net (code "68") (name "Net-(Q3-C)") (class "Default")
      (node (ref "Q3") (pin "1") (pinfunction "C_1") (pintype "passive"))
      (node (ref "R1") (pin "1") (pinfunction "1_1") (pintype "passive"))
    )
    (net (code "69") (name "Net-(Q4-G)") (class "Default")
      (node (ref "Q4") (pin "1") (pinfunction "G_1") (pintype "passive"))
      (node (ref "Q6") (pin "1") (pinfunction "C_1") (pintype "passive"))
      (node (ref "R6") (pin "2") (pinfunction "2_2") (pintype "passive"))
    )
    (net (code "70") (name "Net-(Q5-B)") (class "Default")
      (node (ref "Q5") (pin "2") (pinfunction "B_2") (pintype "passive"))
      (node (ref "R4") (pin "2") (pinfunction "2_2") (pintype "passive"))
    )
    (net (code "71") (name "Net-(Q5-C)") (class "Default")
      (node (ref "Q5") (pin "1") (pinfunction "C_1") (pintype "passive"))
      (node (ref "R5") (pin "1") (pinfunction "1_1") (pintype "passive"))
      (node (ref "R7") (pin "1") (pinfunction "1_1") (pintype "passive"))
    )
    (net (code "72") (name "Net-(Q6-B)") (class "Default")
      (node (ref "Q6") (pin "2") (pinfunction "B_2") (pintype "passive"))
      (node (ref "R7") (pin "2") (pinfunction "2_2") (pintype "passive"))
    )
    (net (code "73") (name "Net-(Q7-B)") (class "Default")
      (node (ref "Q7") (pin "2") (pinfunction "B_2") (pintype "passive"))
      (node (ref "R8") (pin "2") (pinfunction "2_2") (pintype "passive"))
    )
    (net (code "74") (name "Net-(Q8-C)") (class "Default")
      (node (ref "JP2") (pin "2") (pinfunction "2_2") (pintype "passive"))
      (node (ref "JP3") (pin "2") (pinfunction "2_2") (pintype "passive"))
      (node (ref "Q8") (pin "1") (pinfunction "C_1") (pintype "passive"))
    )
    (net (code "75") (name "Net-(Q8-E)") (class "Default")
      (node (ref "Q8") (pin "3") (pinfunction "E_3") (pintype "passive"))
      (node (ref "R16") (pin "2") (pinfunction "2_2") (pintype "passive"))
    )
    (net (code "76") (name "Net-(Q9-C)") (class "Default")
      (node (ref "JP2") (pin "3") (pinfunction "3_3") (pintype "passive"))
      (node (ref "JP3") (pin "3") (pinfunction "3_3") (pintype "passive"))
      (node (ref "Q9") (pin "1") (pinfunction "C_1") (pintype "passive"))
    )
    (net (code "77") (name "Net-(Q9-E)") (class "Default")
      (node (ref "Q9") (pin "3") (pinfunction "E_3") (pintype "passive"))
      (node (ref "R17") (pin "2") (pinfunction "2_2") (pintype "passive"))
    )
    (net (code "78") (name "Net-(Q10-B)") (class "Default")
      (node (ref "Q10") (pin "2") (pinfunction "B_2") (pintype "passive"))
      (node (ref "R15") (pin "2") (pinfunction "2_2") (pintype "passive"))
    )
    (net (code "79") (name "Net-(U2-A)") (class "Default")
      (node (ref "R9") (pin "2") (pinfunction "2_2") (pintype "passive"))
      (node (ref "U2") (pin "1") (pinfunction "A_1") (pintype "passive"))
      (node (ref "U4") (pin "2") (pinfunction "K_2") (pintype "passive"))
    )
    (net (code "80") (name "unconnected-(C3---Pad2)") (class "Default")
      (node (ref "C3") (pin "2") (pinfunction "-_2") (pintype "passive"))
    )
    (net (code "81") (name "unconnected-(Q1-D-Pad2)") (class "Default")
      (node (ref "Q1") (pin "2") (pinfunction "D_2") (pintype "passive"))
    )
    (net (code "82") (name "unconnected-(Q4-D-Pad2)") (class "Default")
      (node (ref "Q4") (pin "2") (pinfunction "D_2") (pintype "passive"))
    )
    (net (code "83") (name "unconnected-(U1-PB3_(ADC2)-Pad3)") (class "Default")
      (node (ref "U1") (pin "3") (pinfunction "PB3_(ADC2)_3") (pintype "bidirectional"))
    )
    (net (code "84") (name "unconnected-(U3-TAB-Pad4)") (class "Default")
      (node (ref "U3") (pin "4") (pinfunction "TAB_4") (pintype "power_in"))
    )
  )
)
